# DC309A_CPLD.net
KiCad netlist of a schematic drawn in Altium Designer
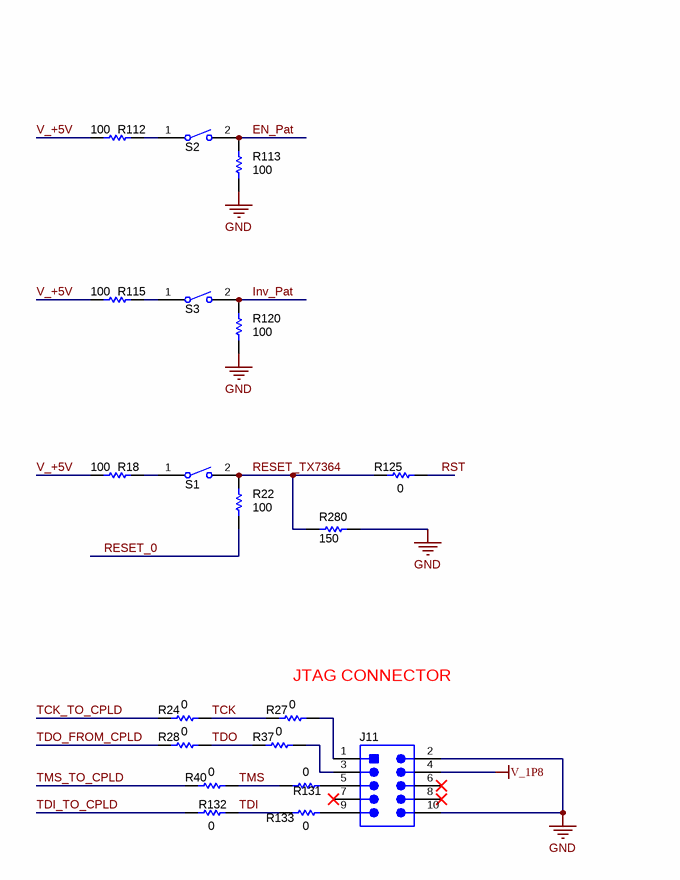
[diagram p0: DC309A_CPLD.SchDoc, top left]
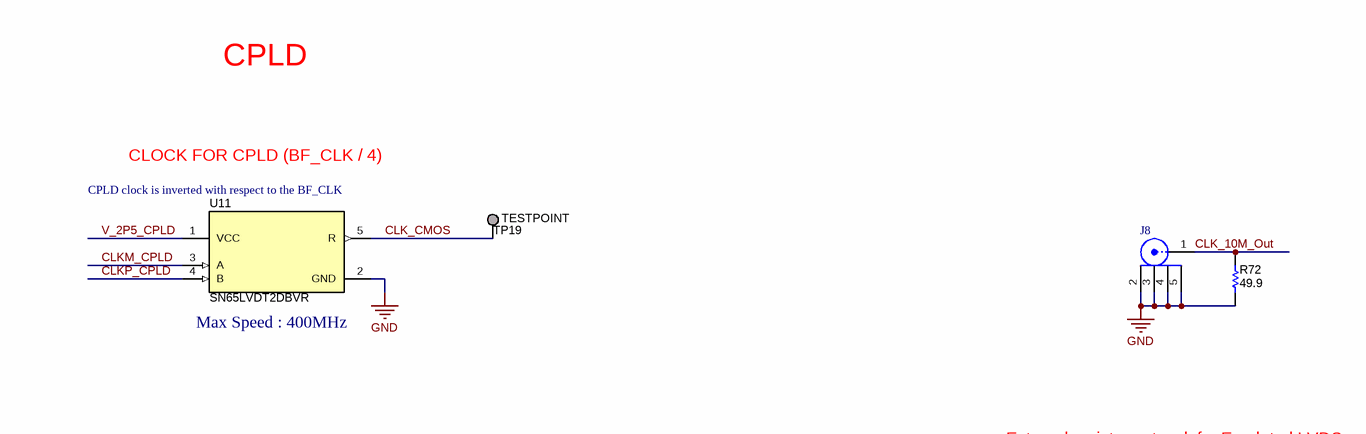
[diagram p1: DC309A_CPLD.SchDoc, top right]
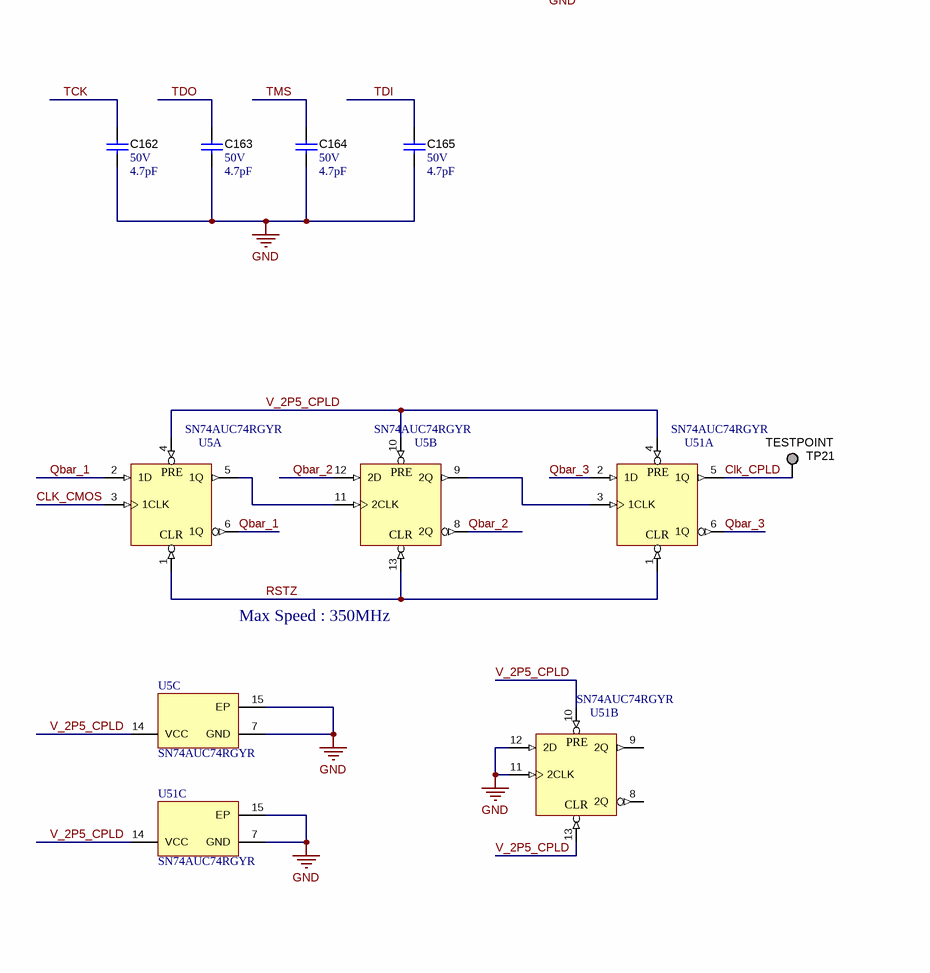
[diagram p2: DC309A_CPLD.SchDoc, bottom left]
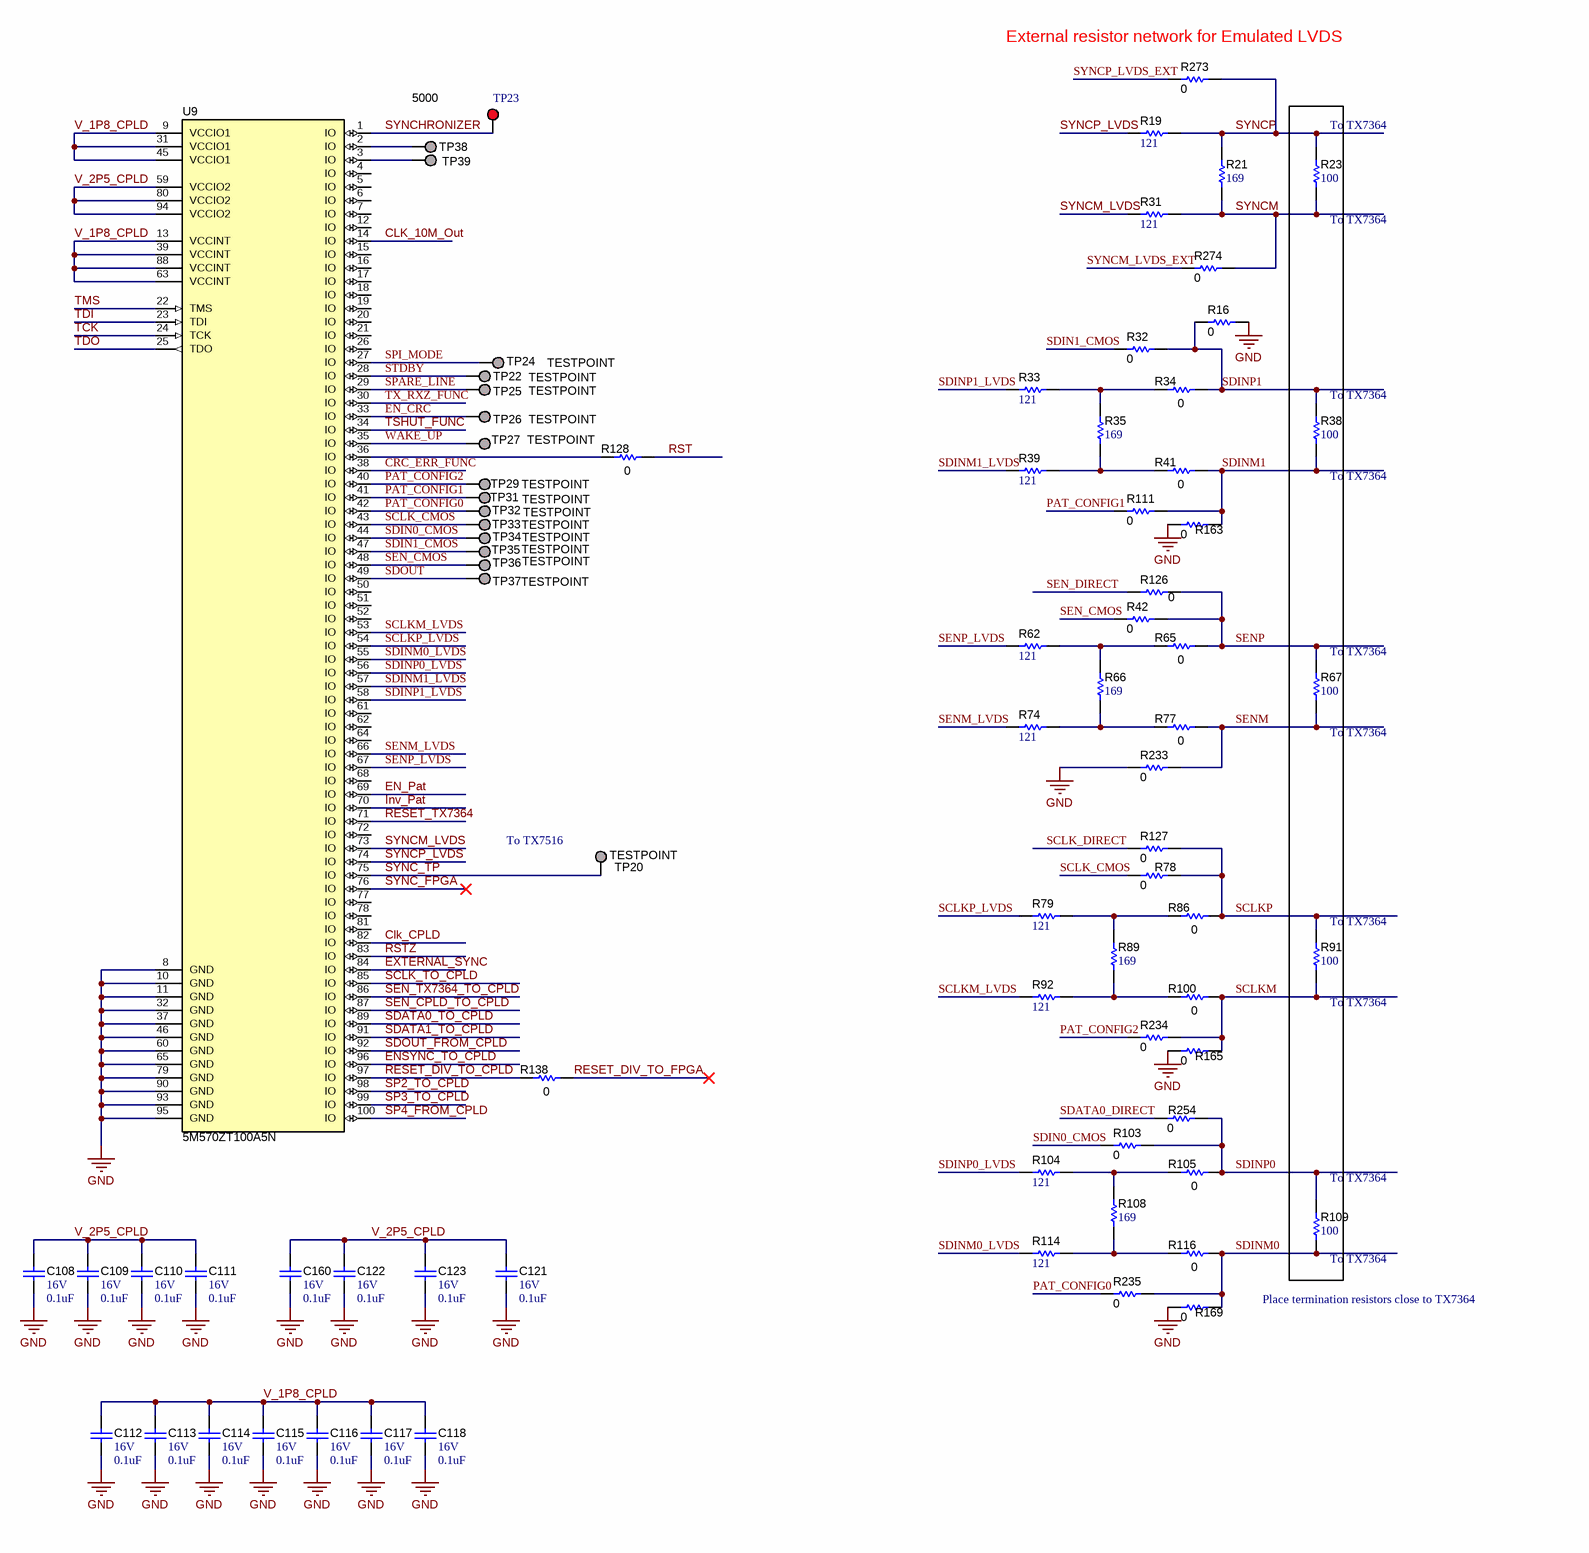
[diagram p3: DC309A_CPLD.SchDoc, bottom right]

(export (version "E")
  (design (tool "Eeschema 10.0.6"))
  (components
    (comp (ref "C108")
      (value "0402YC104KAT2A")
      (footprint "0402")
      (description "CAP, CERM, 0.1 uF, 16 V, +/- 10%, X7R, 0402")
      (fields
        (field (name "MANUFACTURER") "AVX")
        (field (name "VDC_V") "16V")
        (field (name "VALUEDISPLAYED") "0.1uF")
        (field (name "PUBLISHER") "Texas Instruments")
      )
      (libsource (lib "Altium Vault - TI") (part "Capacitor"))
    )
    (comp (ref "C109")
      (value "0402YC104KAT2A")
      (footprint "0402")
      (description "CAP, CERM, 0.1 uF, 16 V, +/- 10%, X7R, 0402")
      (fields
        (field (name "MANUFACTURER") "AVX")
        (field (name "VDC_V") "16V")
        (field (name "VALUEDISPLAYED") "0.1uF")
        (field (name "PUBLISHER") "Texas Instruments")
      )
      (libsource (lib "Altium Vault - TI") (part "Capacitor"))
    )
    (comp (ref "C110")
      (value "0402YC104KAT2A")
      (footprint "0402")
      (description "CAP, CERM, 0.1 uF, 16 V, +/- 10%, X7R, 0402")
      (fields
        (field (name "MANUFACTURER") "AVX")
        (field (name "VDC_V") "16V")
        (field (name "VALUEDISPLAYED") "0.1uF")
        (field (name "PUBLISHER") "Texas Instruments")
      )
      (libsource (lib "Altium Vault - TI") (part "Capacitor"))
    )
    (comp (ref "C111")
      (value "0402YC104KAT2A")
      (footprint "0402")
      (description "CAP, CERM, 0.1 uF, 16 V, +/- 10%, X7R, 0402")
      (fields
        (field (name "MANUFACTURER") "AVX")
        (field (name "VDC_V") "16V")
        (field (name "VALUEDISPLAYED") "0.1uF")
        (field (name "PUBLISHER") "Texas Instruments")
      )
      (libsource (lib "Altium Vault - TI") (part "Capacitor"))
    )
    (comp (ref "C112")
      (value "0402YC104KAT2A")
      (footprint "0402")
      (description "CAP, CERM, 0.1 uF, 16 V, +/- 10%, X7R, 0402")
      (fields
        (field (name "MANUFACTURER") "AVX")
        (field (name "VDC_V") "16V")
        (field (name "VALUEDISPLAYED") "0.1uF")
        (field (name "PUBLISHER") "Texas Instruments")
      )
      (libsource (lib "Altium Vault - TI") (part "Capacitor"))
    )
    (comp (ref "C113")
      (value "0402YC104KAT2A")
      (footprint "0402")
      (description "CAP, CERM, 0.1 uF, 16 V, +/- 10%, X7R, 0402")
      (fields
        (field (name "MANUFACTURER") "AVX")
        (field (name "VDC_V") "16V")
        (field (name "VALUEDISPLAYED") "0.1uF")
        (field (name "PUBLISHER") "Texas Instruments")
      )
      (libsource (lib "Altium Vault - TI") (part "Capacitor"))
    )
    (comp (ref "C114")
      (value "0402YC104KAT2A")
      (footprint "0402")
      (description "CAP, CERM, 0.1 uF, 16 V, +/- 10%, X7R, 0402")
      (fields
        (field (name "MANUFACTURER") "AVX")
        (field (name "VDC_V") "16V")
        (field (name "VALUEDISPLAYED") "0.1uF")
        (field (name "PUBLISHER") "Texas Instruments")
      )
      (libsource (lib "Altium Vault - TI") (part "Capacitor"))
    )
    (comp (ref "C115")
      (value "0402YC104KAT2A")
      (footprint "0402")
      (description "CAP, CERM, 0.1 uF, 16 V, +/- 10%, X7R, 0402")
      (fields
        (field (name "MANUFACTURER") "AVX")
        (field (name "VDC_V") "16V")
        (field (name "VALUEDISPLAYED") "0.1uF")
        (field (name "PUBLISHER") "Texas Instruments")
      )
      (libsource (lib "Altium Vault - TI") (part "Capacitor"))
    )
    (comp (ref "C116")
      (value "0402YC104KAT2A")
      (footprint "0402")
      (description "CAP, CERM, 0.1 uF, 16 V, +/- 10%, X7R, 0402")
      (fields
        (field (name "MANUFACTURER") "AVX")
        (field (name "VDC_V") "16V")
        (field (name "VALUEDISPLAYED") "0.1uF")
        (field (name "PUBLISHER") "Texas Instruments")
      )
      (libsource (lib "Altium Vault - TI") (part "Capacitor"))
    )
    (comp (ref "C117")
      (value "0402YC104KAT2A")
      (footprint "0402")
      (description "CAP, CERM, 0.1 uF, 16 V, +/- 10%, X7R, 0402")
      (fields
        (field (name "MANUFACTURER") "AVX")
        (field (name "VDC_V") "16V")
        (field (name "VALUEDISPLAYED") "0.1uF")
        (field (name "PUBLISHER") "Texas Instruments")
      )
      (libsource (lib "Altium Vault - TI") (part "Capacitor"))
    )
    (comp (ref "C118")
      (value "0402YC104KAT2A")
      (footprint "0402")
      (description "CAP, CERM, 0.1 uF, 16 V, +/- 10%, X7R, 0402")
      (fields
        (field (name "MANUFACTURER") "AVX")
        (field (name "VDC_V") "16V")
        (field (name "VALUEDISPLAYED") "0.1uF")
        (field (name "PUBLISHER") "Texas Instruments")
      )
      (libsource (lib "Altium Vault - TI") (part "Capacitor"))
    )
    (comp (ref "C121")
      (value "0402YC104KAT2A")
      (footprint "0402")
      (description "CAP, CERM, 0.1 uF, 16 V, +/- 10%, X7R, 0402")
      (fields
        (field (name "MANUFACTURER") "AVX")
        (field (name "VDC_V") "16V")
        (field (name "VALUEDISPLAYED") "0.1uF")
        (field (name "PUBLISHER") "Texas Instruments")
      )
      (libsource (lib "Altium Vault - TI") (part "Capacitor"))
    )
    (comp (ref "C122")
      (value "0402YC104KAT2A")
      (footprint "0402")
      (description "CAP, CERM, 0.1 uF, 16 V, +/- 10%, X7R, 0402")
      (fields
        (field (name "MANUFACTURER") "AVX")
        (field (name "VDC_V") "16V")
        (field (name "VALUEDISPLAYED") "0.1uF")
        (field (name "PUBLISHER") "Texas Instruments")
      )
      (libsource (lib "Altium Vault - TI") (part "Capacitor"))
    )
    (comp (ref "C123")
      (value "0402YC104KAT2A")
      (footprint "0402")
      (description "CAP, CERM, 0.1 uF, 16 V, +/- 10%, X7R, 0402")
      (fields
        (field (name "MANUFACTURER") "AVX")
        (field (name "VDC_V") "16V")
        (field (name "VALUEDISPLAYED") "0.1uF")
        (field (name "PUBLISHER") "Texas Instruments")
      )
      (libsource (lib "Altium Vault - TI") (part "Capacitor"))
    )
    (comp (ref "C160")
      (value "0402YC104KAT2A")
      (footprint "0402")
      (description "CAP, CERM, 0.1 uF, 16 V, +/- 10%, X7R, 0402")
      (fields
        (field (name "MANUFACTURER") "AVX")
        (field (name "VDC_V") "16V")
        (field (name "VALUEDISPLAYED") "0.1uF")
        (field (name "PUBLISHER") "Texas Instruments")
      )
      (libsource (lib "Altium Vault - TI") (part "Capacitor"))
    )
    (comp (ref "C162")
      (value "06035A4R7CAT2A")
      (footprint "0603")
      (description "CAP, CERM, 4.7 pF, 50 V, +/- 5%, C0G/NP0, 0603")
      (fields
        (field (name "MANUFACTURER") "AVX")
        (field (name "VDC_V") "50V")
        (field (name "VALUEDISPLAYED") "4.7pF")
        (field (name "PUBLISHER") "Texas Instruments")
      )
      (libsource (lib "Altium Vault - TI") (part "Capacitor"))
    )
    (comp (ref "C163")
      (value "06035A4R7CAT2A")
      (footprint "0603")
      (description "CAP, CERM, 4.7 pF, 50 V, +/- 5%, C0G/NP0, 0603")
      (fields
        (field (name "MANUFACTURER") "AVX")
        (field (name "VDC_V") "50V")
        (field (name "VALUEDISPLAYED") "4.7pF")
        (field (name "PUBLISHER") "Texas Instruments")
      )
      (libsource (lib "Altium Vault - TI") (part "Capacitor"))
    )
    (comp (ref "C164")
      (value "06035A4R7CAT2A")
      (footprint "0603")
      (description "CAP, CERM, 4.7 pF, 50 V, +/- 5%, C0G/NP0, 0603")
      (fields
        (field (name "MANUFACTURER") "AVX")
        (field (name "VDC_V") "50V")
        (field (name "VALUEDISPLAYED") "4.7pF")
        (field (name "PUBLISHER") "Texas Instruments")
      )
      (libsource (lib "Altium Vault - TI") (part "Capacitor"))
    )
    (comp (ref "C165")
      (value "06035A4R7CAT2A")
      (footprint "0603")
      (description "CAP, CERM, 4.7 pF, 50 V, +/- 5%, C0G/NP0, 0603")
      (fields
        (field (name "MANUFACTURER") "AVX")
        (field (name "VDC_V") "50V")
        (field (name "VALUEDISPLAYED") "4.7pF")
        (field (name "PUBLISHER") "Texas Instruments")
      )
      (libsource (lib "Altium Vault - TI") (part "Capacitor"))
    )
    (comp (ref "J8")
      (value "901-144-8RFX")
      (footprint "AMPHENOL_901-144-8RFX")
      (description "SMA Straight Jack, Gold, 50 Ohm, TH")
      (fields (field (name "MANUFACTURER") "Amphenol RF") (field (name "PUBLISHER") "Texas Instruments"))
      (libsource (lib "Altium Vault - TI") (part "SMA_Contact1_GND2345"))
    )
    (comp (ref "J11")
      (value "TSW-105-07-F-D")
      (footprint "Samtec_TSW-105-07-x-D")
      (description "Header, 2.54mm, 5x2, Gold, Black, TH")
      (fields (field (name "MANUFACTURER") "Samtec"))
      (libsource (lib "Altium Vault - TI") (part "Header_5x2"))
    )
    (comp (ref "R16")
      (value "0")
      (footprint "0402")
      (description "RES, 0, 5%, 0.1 W, AEC-Q200 Grade 0, 0402")
      (fields (field (name "PARTNUMBER") "ERJ-2GE0R00X") (field (name "MANUFACTURER") "Panasonic"))
      (libsource (lib "Altium Vault - TI") (part "CMP-0026992-3"))
    )
    (comp (ref "R18")
      (value "Resistor")
      (footprint "0402")
      (description "RES, 100, 5%, 0.063 W, AEC-Q200 Grade 0, 0402")
      (fields
        (field (name "PARTNUMBER") "CRCW0402100RJNED")
        (field (name "MANUFACTURER") "Vishay-Dale")
        (field (name "RES_OHM") "100")
      )
      (libsource (lib "Altium Vault - TI") (part "CMP-0026824-3"))
    )
    (comp (ref "R19")
      (value "CRCW0402121RFKED")
      (footprint "0402")
      (description "RES, 121, 1%, 0.063 W, AEC-Q200 Grade 0, 0402")
      (fields (field (name "MANUFACTURER") "Vishay-Dale") (field (name "VALUEDISPLAYED") "121"))
      (libsource (lib "Altium Vault - TI") (part "Resistor"))
    )
    (comp (ref "R21")
      (value "CRCW0402169RFKED")
      (footprint "0402")
      (description "RES, 169, 1%, 0.063 W, AEC-Q200 Grade 0, 0402")
      (fields (field (name "MANUFACTURER") "Vishay-Dale") (field (name "VALUEDISPLAYED") "169"))
      (libsource (lib "Altium Vault - TI") (part "Resistor"))
    )
    (comp (ref "R22")
      (value "Resistor")
      (footprint "0402")
      (description "RES, 100, 5%, 0.063 W, AEC-Q200 Grade 0, 0402")
      (fields
        (field (name "PARTNUMBER") "CRCW0402100RJNED")
        (field (name "MANUFACTURER") "Vishay-Dale")
        (field (name "RES_OHM") "100")
      )
      (libsource (lib "Altium Vault - TI") (part "CMP-0026824-3"))
    )
    (comp (ref "R23")
      (value "CRCW0402100RFKED")
      (footprint "0402")
      (description "RES, 100, 1%, 0.063 W, AEC-Q200 Grade 0, 0402")
      (fields (field (name "MANUFACTURER") "Vishay-Dale") (field (name "VALUEDISPLAYED") "100"))
      (libsource (lib "Altium Vault - TI") (part "Resistor"))
    )
    (comp (ref "R24")
      (value "0")
      (footprint "0402")
      (description "RES, 0, 5%, 0.1 W, AEC-Q200 Grade 0, 0402")
      (fields (field (name "PARTNUMBER") "ERJ-2GE0R00X") (field (name "MANUFACTURER") "Panasonic"))
      (libsource (lib "Altium Vault - TI") (part "CMP-0026992-3"))
    )
    (comp (ref "R27")
      (value "0")
      (footprint "0402")
      (description "RES, 0, 5%, 0.1 W, AEC-Q200 Grade 0, 0402")
      (fields (field (name "PARTNUMBER") "ERJ-2GE0R00X") (field (name "MANUFACTURER") "Panasonic"))
      (libsource (lib "Altium Vault - TI") (part "CMP-0026992-3"))
    )
    (comp (ref "R28")
      (value "0")
      (footprint "0402")
      (description "RES, 0, 5%, 0.1 W, AEC-Q200 Grade 0, 0402")
      (fields (field (name "PARTNUMBER") "ERJ-2GE0R00X") (field (name "MANUFACTURER") "Panasonic"))
      (libsource (lib "Altium Vault - TI") (part "CMP-0026992-3"))
    )
    (comp (ref "R31")
      (value "CRCW0402121RFKED")
      (footprint "0402")
      (description "RES, 121, 1%, 0.063 W, AEC-Q200 Grade 0, 0402")
      (fields (field (name "MANUFACTURER") "Vishay-Dale") (field (name "VALUEDISPLAYED") "121"))
      (libsource (lib "Altium Vault - TI") (part "Resistor"))
    )
    (comp (ref "R32")
      (value "0")
      (footprint "0402")
      (description "RES, 0, 5%, 0.1 W, AEC-Q200 Grade 0, 0402")
      (fields (field (name "PARTNUMBER") "ERJ-2GE0R00X") (field (name "MANUFACTURER") "Panasonic"))
      (libsource (lib "Altium Vault - TI") (part "CMP-0026992-3"))
    )
    (comp (ref "R33")
      (value "CRCW0402121RFKED")
      (footprint "0402")
      (description "RES, 121, 1%, 0.063 W, AEC-Q200 Grade 0, 0402")
      (fields (field (name "MANUFACTURER") "Vishay-Dale") (field (name "VALUEDISPLAYED") "121"))
      (libsource (lib "Altium Vault - TI") (part "Resistor"))
    )
    (comp (ref "R34")
      (value "0")
      (footprint "0402")
      (description "RES, 0, 5%, 0.1 W, AEC-Q200 Grade 0, 0402")
      (fields (field (name "PARTNUMBER") "ERJ-2GE0R00X") (field (name "MANUFACTURER") "Panasonic"))
      (libsource (lib "Altium Vault - TI") (part "CMP-0026992-3"))
    )
    (comp (ref "R35")
      (value "CRCW0402169RFKED")
      (footprint "0402")
      (description "RES, 169, 1%, 0.063 W, AEC-Q200 Grade 0, 0402")
      (fields (field (name "MANUFACTURER") "Vishay-Dale") (field (name "VALUEDISPLAYED") "169"))
      (libsource (lib "Altium Vault - TI") (part "Resistor"))
    )
    (comp (ref "R37")
      (value "0")
      (footprint "0402")
      (description "RES, 0, 5%, 0.1 W, AEC-Q200 Grade 0, 0402")
      (fields (field (name "PARTNUMBER") "ERJ-2GE0R00X") (field (name "MANUFACTURER") "Panasonic"))
      (libsource (lib "Altium Vault - TI") (part "CMP-0026992-3"))
    )
    (comp (ref "R38")
      (value "CRCW0402100RFKED")
      (footprint "0402")
      (description "RES, 100, 1%, 0.063 W, AEC-Q200 Grade 0, 0402")
      (fields (field (name "MANUFACTURER") "Vishay-Dale") (field (name "VALUEDISPLAYED") "100"))
      (libsource (lib "Altium Vault - TI") (part "Resistor"))
    )
    (comp (ref "R39")
      (value "CRCW0402121RFKED")
      (footprint "0402")
      (description "RES, 121, 1%, 0.063 W, AEC-Q200 Grade 0, 0402")
      (fields (field (name "MANUFACTURER") "Vishay-Dale") (field (name "VALUEDISPLAYED") "121"))
      (libsource (lib "Altium Vault - TI") (part "Resistor"))
    )
    (comp (ref "R40")
      (value "0")
      (footprint "0402")
      (description "RES, 0, 5%, 0.1 W, AEC-Q200 Grade 0, 0402")
      (fields (field (name "PARTNUMBER") "ERJ-2GE0R00X") (field (name "MANUFACTURER") "Panasonic"))
      (libsource (lib "Altium Vault - TI") (part "CMP-0026992-3"))
    )
    (comp (ref "R41")
      (value "0")
      (footprint "0402")
      (description "RES, 0, 5%, 0.1 W, AEC-Q200 Grade 0, 0402")
      (fields (field (name "PARTNUMBER") "ERJ-2GE0R00X") (field (name "MANUFACTURER") "Panasonic"))
      (libsource (lib "Altium Vault - TI") (part "CMP-0026992-3"))
    )
    (comp (ref "R42")
      (value "0")
      (footprint "0402")
      (description "RES, 0, 5%, 0.1 W, AEC-Q200 Grade 0, 0402")
      (fields (field (name "PARTNUMBER") "ERJ-2GE0R00X") (field (name "MANUFACTURER") "Panasonic"))
      (libsource (lib "Altium Vault - TI") (part "CMP-0026992-3"))
    )
    (comp (ref "R62")
      (value "CRCW0402121RFKED")
      (footprint "0402")
      (description "RES, 121, 1%, 0.063 W, AEC-Q200 Grade 0, 0402")
      (fields (field (name "MANUFACTURER") "Vishay-Dale") (field (name "VALUEDISPLAYED") "121"))
      (libsource (lib "Altium Vault - TI") (part "Resistor"))
    )
    (comp (ref "R65")
      (value "0")
      (footprint "0402")
      (description "RES, 0, 5%, 0.1 W, AEC-Q200 Grade 0, 0402")
      (fields (field (name "PARTNUMBER") "ERJ-2GE0R00X") (field (name "MANUFACTURER") "Panasonic"))
      (libsource (lib "Altium Vault - TI") (part "CMP-0026992-3"))
    )
    (comp (ref "R66")
      (value "CRCW0402169RFKED")
      (footprint "0402")
      (description "RES, 169, 1%, 0.063 W, AEC-Q200 Grade 0, 0402")
      (fields (field (name "MANUFACTURER") "Vishay-Dale") (field (name "VALUEDISPLAYED") "169"))
      (libsource (lib "Altium Vault - TI") (part "Resistor"))
    )
    (comp (ref "R67")
      (value "CRCW0402100RFKED")
      (footprint "0402")
      (description "RES, 100, 1%, 0.063 W, AEC-Q200 Grade 0, 0402")
      (fields (field (name "MANUFACTURER") "Vishay-Dale") (field (name "VALUEDISPLAYED") "100"))
      (libsource (lib "Altium Vault - TI") (part "Resistor"))
    )
    (comp (ref "R72")
      (value "TNPW060349R9BEEA")
      (footprint "TNPW0603")
      (description "RES, 49.9, 0.1%, 0.1 W, AEC-Q200 Grade 1, 0603")
      (fields
        (field (name "MANUFACTURER") "Vishay-Dale")
        (field (name "VALUEDISPLAYED") "49.9")
        (field (name "PUBLISHER") "Texas Instruments")
      )
      (libsource (lib "Altium Vault - TI") (part "Resistor"))
    )
    (comp (ref "R74")
      (value "CRCW0402121RFKED")
      (footprint "0402")
      (description "RES, 121, 1%, 0.063 W, AEC-Q200 Grade 0, 0402")
      (fields (field (name "MANUFACTURER") "Vishay-Dale") (field (name "VALUEDISPLAYED") "121"))
      (libsource (lib "Altium Vault - TI") (part "Resistor"))
    )
    (comp (ref "R77")
      (value "0")
      (footprint "0402")
      (description "RES, 0, 5%, 0.1 W, AEC-Q200 Grade 0, 0402")
      (fields (field (name "PARTNUMBER") "ERJ-2GE0R00X") (field (name "MANUFACTURER") "Panasonic"))
      (libsource (lib "Altium Vault - TI") (part "CMP-0026992-3"))
    )
    (comp (ref "R78")
      (value "0")
      (footprint "0402")
      (description "RES, 0, 5%, 0.1 W, AEC-Q200 Grade 0, 0402")
      (fields (field (name "PARTNUMBER") "ERJ-2GE0R00X") (field (name "MANUFACTURER") "Panasonic"))
      (libsource (lib "Altium Vault - TI") (part "CMP-0026992-3"))
    )
    (comp (ref "R79")
      (value "CRCW0402121RFKED")
      (footprint "0402")
      (description "RES, 121, 1%, 0.063 W, AEC-Q200 Grade 0, 0402")
      (fields (field (name "MANUFACTURER") "Vishay-Dale") (field (name "VALUEDISPLAYED") "121"))
      (libsource (lib "Altium Vault - TI") (part "Resistor"))
    )
    (comp (ref "R86")
      (value "0")
      (footprint "0402")
      (description "RES, 0, 5%, 0.1 W, AEC-Q200 Grade 0, 0402")
      (fields (field (name "PARTNUMBER") "ERJ-2GE0R00X") (field (name "MANUFACTURER") "Panasonic"))
      (libsource (lib "Altium Vault - TI") (part "CMP-0026992-3"))
    )
    (comp (ref "R89")
      (value "CRCW0402169RFKED")
      (footprint "0402")
      (description "RES, 169, 1%, 0.063 W, AEC-Q200 Grade 0, 0402")
      (fields (field (name "MANUFACTURER") "Vishay-Dale") (field (name "VALUEDISPLAYED") "169"))
      (libsource (lib "Altium Vault - TI") (part "Resistor"))
    )
    (comp (ref "R91")
      (value "CRCW0402100RFKED")
      (footprint "0402")
      (description "RES, 100, 1%, 0.063 W, AEC-Q200 Grade 0, 0402")
      (fields (field (name "MANUFACTURER") "Vishay-Dale") (field (name "VALUEDISPLAYED") "100"))
      (libsource (lib "Altium Vault - TI") (part "Resistor"))
    )
    (comp (ref "R92")
      (value "CRCW0402121RFKED")
      (footprint "0402")
      (description "RES, 121, 1%, 0.063 W, AEC-Q200 Grade 0, 0402")
      (fields (field (name "MANUFACTURER") "Vishay-Dale") (field (name "VALUEDISPLAYED") "121"))
      (libsource (lib "Altium Vault - TI") (part "Resistor"))
    )
    (comp (ref "R100")
      (value "0")
      (footprint "0402")
      (description "RES, 0, 5%, 0.1 W, AEC-Q200 Grade 0, 0402")
      (fields (field (name "PARTNUMBER") "ERJ-2GE0R00X") (field (name "MANUFACTURER") "Panasonic"))
      (libsource (lib "Altium Vault - TI") (part "CMP-0026992-3"))
    )
    (comp (ref "R103")
      (value "0")
      (footprint "0402")
      (description "RES, 0, 5%, 0.1 W, AEC-Q200 Grade 0, 0402")
      (fields (field (name "PARTNUMBER") "ERJ-2GE0R00X") (field (name "MANUFACTURER") "Panasonic"))
      (libsource (lib "Altium Vault - TI") (part "CMP-0026992-3"))
    )
    (comp (ref "R104")
      (value "CRCW0402121RFKED")
      (footprint "0402")
      (description "RES, 121, 1%, 0.063 W, AEC-Q200 Grade 0, 0402")
      (fields (field (name "MANUFACTURER") "Vishay-Dale") (field (name "VALUEDISPLAYED") "121"))
      (libsource (lib "Altium Vault - TI") (part "Resistor"))
    )
    (comp (ref "R105")
      (value "0")
      (footprint "0402")
      (description "RES, 0, 5%, 0.1 W, AEC-Q200 Grade 0, 0402")
      (fields (field (name "PARTNUMBER") "ERJ-2GE0R00X") (field (name "MANUFACTURER") "Panasonic"))
      (libsource (lib "Altium Vault - TI") (part "CMP-0026992-3"))
    )
    (comp (ref "R108")
      (value "CRCW0402169RFKED")
      (footprint "0402")
      (description "RES, 169, 1%, 0.063 W, AEC-Q200 Grade 0, 0402")
      (fields (field (name "MANUFACTURER") "Vishay-Dale") (field (name "VALUEDISPLAYED") "169"))
      (libsource (lib "Altium Vault - TI") (part "Resistor"))
    )
    (comp (ref "R109")
      (value "CRCW0402100RFKED")
      (footprint "0402")
      (description "RES, 100, 1%, 0.063 W, AEC-Q200 Grade 0, 0402")
      (fields (field (name "MANUFACTURER") "Vishay-Dale") (field (name "VALUEDISPLAYED") "100"))
      (libsource (lib "Altium Vault - TI") (part "Resistor"))
    )
    (comp (ref "R111")
      (value "0")
      (footprint "0402")
      (description "RES, 0, 5%, 0.1 W, AEC-Q200 Grade 0, 0402")
      (fields (field (name "PARTNUMBER") "ERJ-2GE0R00X") (field (name "MANUFACTURER") "Panasonic"))
      (libsource (lib "Altium Vault - TI") (part "CMP-0026992-3"))
    )
    (comp (ref "R112")
      (value "Resistor")
      (footprint "0402")
      (description "RES, 100, 5%, 0.063 W, AEC-Q200 Grade 0, 0402")
      (fields
        (field (name "PARTNUMBER") "CRCW0402100RJNED")
        (field (name "MANUFACTURER") "Vishay-Dale")
        (field (name "RES_OHM") "100")
      )
      (libsource (lib "Altium Vault - TI") (part "CMP-0026824-3"))
    )
    (comp (ref "R113")
      (value "Resistor")
      (footprint "0402")
      (description "RES, 100, 5%, 0.063 W, AEC-Q200 Grade 0, 0402")
      (fields
        (field (name "PARTNUMBER") "CRCW0402100RJNED")
        (field (name "MANUFACTURER") "Vishay-Dale")
        (field (name "RES_OHM") "100")
      )
      (libsource (lib "Altium Vault - TI") (part "CMP-0026824-3"))
    )
    (comp (ref "R114")
      (value "CRCW0402121RFKED")
      (footprint "0402")
      (description "RES, 121, 1%, 0.063 W, AEC-Q200 Grade 0, 0402")
      (fields (field (name "MANUFACTURER") "Vishay-Dale") (field (name "VALUEDISPLAYED") "121"))
      (libsource (lib "Altium Vault - TI") (part "Resistor"))
    )
    (comp (ref "R115")
      (value "Resistor")
      (footprint "0402")
      (description "RES, 100, 5%, 0.063 W, AEC-Q200 Grade 0, 0402")
      (fields
        (field (name "PARTNUMBER") "CRCW0402100RJNED")
        (field (name "MANUFACTURER") "Vishay-Dale")
        (field (name "RES_OHM") "100")
      )
      (libsource (lib "Altium Vault - TI") (part "CMP-0026824-3"))
    )
    (comp (ref "R116")
      (value "0")
      (footprint "0402")
      (description "RES, 0, 5%, 0.1 W, AEC-Q200 Grade 0, 0402")
      (fields (field (name "PARTNUMBER") "ERJ-2GE0R00X") (field (name "MANUFACTURER") "Panasonic"))
      (libsource (lib "Altium Vault - TI") (part "CMP-0026992-3"))
    )
    (comp (ref "R120")
      (value "Resistor")
      (footprint "0402")
      (description "RES, 100, 5%, 0.063 W, AEC-Q200 Grade 0, 0402")
      (fields
        (field (name "PARTNUMBER") "CRCW0402100RJNED")
        (field (name "MANUFACTURER") "Vishay-Dale")
        (field (name "RES_OHM") "100")
      )
      (libsource (lib "Altium Vault - TI") (part "CMP-0026824-3"))
    )
    (comp (ref "R125")
      (value "0")
      (footprint "0402")
      (description "RES, 0, 5%, 0.1 W, AEC-Q200 Grade 0, 0402")
      (fields (field (name "PARTNUMBER") "ERJ-2GE0R00X") (field (name "MANUFACTURER") "Panasonic"))
      (libsource (lib "Altium Vault - TI") (part "CMP-0026992-3"))
    )
    (comp (ref "R126")
      (value "0")
      (footprint "0402")
      (description "RES, 0, 5%, 0.1 W, AEC-Q200 Grade 0, 0402")
      (fields (field (name "PARTNUMBER") "ERJ-2GE0R00X") (field (name "MANUFACTURER") "Panasonic"))
      (libsource (lib "Altium Vault - TI") (part "CMP-0026992-3"))
    )
    (comp (ref "R127")
      (value "0")
      (footprint "0402")
      (description "RES, 0, 5%, 0.1 W, AEC-Q200 Grade 0, 0402")
      (fields (field (name "PARTNUMBER") "ERJ-2GE0R00X") (field (name "MANUFACTURER") "Panasonic"))
      (libsource (lib "Altium Vault - TI") (part "CMP-0026992-3"))
    )
    (comp (ref "R128")
      (value "0")
      (footprint "0402")
      (description "RES, 0, 5%, 0.1 W, AEC-Q200 Grade 0, 0402")
      (fields (field (name "PARTNUMBER") "ERJ-2GE0R00X") (field (name "MANUFACTURER") "Panasonic"))
      (libsource (lib "Altium Vault - TI") (part "CMP-0026992-3"))
    )
    (comp (ref "R131")
      (value "0")
      (footprint "0402")
      (description "RES, 0, 5%, 0.1 W, AEC-Q200 Grade 0, 0402")
      (fields (field (name "PARTNUMBER") "ERJ-2GE0R00X") (field (name "MANUFACTURER") "Panasonic"))
      (libsource (lib "Altium Vault - TI") (part "CMP-0026992-3"))
    )
    (comp (ref "R132")
      (value "0")
      (footprint "0402")
      (description "RES, 0, 5%, 0.1 W, AEC-Q200 Grade 0, 0402")
      (fields (field (name "PARTNUMBER") "ERJ-2GE0R00X") (field (name "MANUFACTURER") "Panasonic"))
      (libsource (lib "Altium Vault - TI") (part "CMP-0026992-3"))
    )
    (comp (ref "R133")
      (value "0")
      (footprint "0402")
      (description "RES, 0, 5%, 0.1 W, AEC-Q200 Grade 0, 0402")
      (fields (field (name "PARTNUMBER") "ERJ-2GE0R00X") (field (name "MANUFACTURER") "Panasonic"))
      (libsource (lib "Altium Vault - TI") (part "CMP-0026992-3"))
    )
    (comp (ref "R138")
      (value "0")
      (footprint "0402")
      (description "RES, 0, 5%, 0.1 W, AEC-Q200 Grade 0, 0402")
      (fields (field (name "PARTNUMBER") "ERJ-2GE0R00X") (field (name "MANUFACTURER") "Panasonic"))
      (libsource (lib "Altium Vault - TI") (part "CMP-0026992-3"))
    )
    (comp (ref "R163")
      (value "0")
      (footprint "0402")
      (description "RES, 0, 5%, 0.1 W, AEC-Q200 Grade 0, 0402")
      (fields (field (name "PARTNUMBER") "ERJ-2GE0R00X") (field (name "MANUFACTURER") "Panasonic"))
      (libsource (lib "Altium Vault - TI") (part "CMP-0026992-3"))
    )
    (comp (ref "R165")
      (value "0")
      (footprint "0402")
      (description "RES, 0, 5%, 0.1 W, AEC-Q200 Grade 0, 0402")
      (fields (field (name "PARTNUMBER") "ERJ-2GE0R00X") (field (name "MANUFACTURER") "Panasonic"))
      (libsource (lib "Altium Vault - TI") (part "CMP-0026992-3"))
    )
    (comp (ref "R169")
      (value "0")
      (footprint "0402")
      (description "RES, 0, 5%, 0.1 W, AEC-Q200 Grade 0, 0402")
      (fields (field (name "PARTNUMBER") "ERJ-2GE0R00X") (field (name "MANUFACTURER") "Panasonic"))
      (libsource (lib "Altium Vault - TI") (part "CMP-0026992-3"))
    )
    (comp (ref "R233")
      (value "0")
      (footprint "0402")
      (description "RES, 0, 5%, 0.1 W, AEC-Q200 Grade 0, 0402")
      (fields (field (name "PARTNUMBER") "ERJ-2GE0R00X") (field (name "MANUFACTURER") "Panasonic"))
      (libsource (lib "Altium Vault - TI") (part "CMP-0026992-3"))
    )
    (comp (ref "R234")
      (value "0")
      (footprint "0402")
      (description "RES, 0, 5%, 0.1 W, AEC-Q200 Grade 0, 0402")
      (fields (field (name "PARTNUMBER") "ERJ-2GE0R00X") (field (name "MANUFACTURER") "Panasonic"))
      (libsource (lib "Altium Vault - TI") (part "CMP-0026992-3"))
    )
    (comp (ref "R235")
      (value "0")
      (footprint "0402")
      (description "RES, 0, 5%, 0.1 W, AEC-Q200 Grade 0, 0402")
      (fields (field (name "PARTNUMBER") "ERJ-2GE0R00X") (field (name "MANUFACTURER") "Panasonic"))
      (libsource (lib "Altium Vault - TI") (part "CMP-0026992-3"))
    )
    (comp (ref "R254")
      (value "0")
      (footprint "0402")
      (description "RES, 0, 5%, 0.1 W, AEC-Q200 Grade 0, 0402")
      (fields (field (name "PARTNUMBER") "ERJ-2GE0R00X") (field (name "MANUFACTURER") "Panasonic"))
      (libsource (lib "Altium Vault - TI") (part "CMP-0026992-3"))
    )
    (comp (ref "R273")
      (value "0")
      (footprint "0402")
      (description "RES, 0, 5%, 0.1 W, AEC-Q200 Grade 0, 0402")
      (fields (field (name "PARTNUMBER") "ERJ-2GE0R00X") (field (name "MANUFACTURER") "Panasonic"))
      (libsource (lib "Altium Vault - TI") (part "CMP-0026992-3"))
    )
    (comp (ref "R274")
      (value "0")
      (footprint "0402")
      (description "RES, 0, 5%, 0.1 W, AEC-Q200 Grade 0, 0402")
      (fields (field (name "PARTNUMBER") "ERJ-2GE0R00X") (field (name "MANUFACTURER") "Panasonic"))
      (libsource (lib "Altium Vault - TI") (part "CMP-0026992-3"))
    )
    (comp (ref "R280")
      (value "RT0603BRD07150RL")
      (footprint "0603")
      (description "RES, 150, 0.1%, 0.1 W, 0603")
      (fields
        (field (name "MANUFACTURER") "Yageo America")
        (field (name "VALUEDISPLAYED") "150")
        (field (name "PUBLISHER") "Texas Instruments")
      )
      (libsource (lib "Altium Vault - TI") (part "Resistor"))
    )
    (comp (ref "S1")
      (value "SW_SPST-single")
      (footprint "SW_EVQ5PN04K")
      (description "Switch, SPST-NO, Off-Mom, 0.05 A, 12 VDC, SMD")
      (fields
        (field (name "PARTNUMBER") "EVQ-5PN04K")
        (field (name "MANUFACTURER") "Panasonic")
        (field (name "PUBLISHER") "Texas Instruments")
      )
      (libsource (lib "Altium Vault - TI") (part "SW_SPST-single"))
    )
    (comp (ref "S2")
      (value "SW_SPST-single")
      (footprint "SW_EVQ5PN04K")
      (description "Switch, SPST-NO, Off-Mom, 0.05 A, 12 VDC, SMD")
      (fields
        (field (name "PARTNUMBER") "EVQ-5PN04K")
        (field (name "MANUFACTURER") "Panasonic")
        (field (name "PUBLISHER") "Texas Instruments")
      )
      (libsource (lib "Altium Vault - TI") (part "SW_SPST-single"))
    )
    (comp (ref "S3")
      (value "SW_SPST-single")
      (footprint "SW_EVQ5PN04K")
      (description "Switch, SPST-NO, Off-Mom, 0.05 A, 12 VDC, SMD")
      (fields
        (field (name "PARTNUMBER") "EVQ-5PN04K")
        (field (name "MANUFACTURER") "Panasonic")
        (field (name "PUBLISHER") "Texas Instruments")
      )
      (libsource (lib "Altium Vault - TI") (part "SW_SPST-single"))
    )
    (comp (ref "TP19")
      (value "TESTPOINT")
      (footprint "TP_50MIL-SMT")
      (description "TEST POINT.  No entry in BOM.")
      (libsource (lib "Altium Vault - TI") (part "TESTPOINT"))
    )
    (comp (ref "TP20")
      (value "TESTPOINT")
      (footprint "TP_50MIL-SMT")
      (description "TEST POINT.  No entry in BOM.")
      (libsource (lib "Altium Vault - TI") (part "TESTPOINT"))
    )
    (comp (ref "TP21")
      (value "TESTPOINT")
      (footprint "TP_50MIL-SMT")
      (description "TEST POINT.  No entry in BOM.")
      (libsource (lib "Altium Vault - TI") (part "TESTPOINT"))
    )
    (comp (ref "TP22")
      (value "TESTPOINT")
      (footprint "TP_50MIL-SMT")
      (description "TEST POINT.  No entry in BOM.")
      (libsource (lib "Altium Vault - TI") (part "TESTPOINT"))
    )
    (comp (ref "TP23")
      (value "5000")
      (footprint "Keystone5000")
      (description "Test Point, Miniature, Red, TH")
      (fields
        (field (name "MANUFACTURER") "Keystone Electronics")
        (field (name "PUBLISHER") "Texas Instruments")
      )
      (libsource (lib "Altium Vault - TI") (part "5000"))
    )
    (comp (ref "TP24")
      (value "TESTPOINT")
      (footprint "TP_50MIL-SMT")
      (description "TEST POINT.  No entry in BOM.")
      (libsource (lib "Altium Vault - TI") (part "TESTPOINT"))
    )
    (comp (ref "TP25")
      (value "TESTPOINT")
      (footprint "TP_50MIL-SMT")
      (description "TEST POINT.  No entry in BOM.")
      (libsource (lib "Altium Vault - TI") (part "TESTPOINT"))
    )
    (comp (ref "TP26")
      (value "TESTPOINT")
      (footprint "TP_50MIL-SMT")
      (description "TEST POINT.  No entry in BOM.")
      (libsource (lib "Altium Vault - TI") (part "TESTPOINT"))
    )
    (comp (ref "TP27")
      (value "TESTPOINT")
      (footprint "TP_50MIL-SMT")
      (description "TEST POINT.  No entry in BOM.")
      (libsource (lib "Altium Vault - TI") (part "TESTPOINT"))
    )
    (comp (ref "TP29")
      (value "TESTPOINT")
      (footprint "TP_50MIL-SMT")
      (description "TEST POINT.  No entry in BOM.")
      (libsource (lib "Altium Vault - TI") (part "TESTPOINT"))
    )
    (comp (ref "TP31")
      (value "TESTPOINT")
      (footprint "TP_50MIL-SMT")
      (description "TEST POINT.  No entry in BOM.")
      (libsource (lib "Altium Vault - TI") (part "TESTPOINT"))
    )
    (comp (ref "TP32")
      (value "TESTPOINT")
      (footprint "TP_50MIL-SMT")
      (description "TEST POINT.  No entry in BOM.")
      (libsource (lib "Altium Vault - TI") (part "TESTPOINT"))
    )
    (comp (ref "TP33")
      (value "TESTPOINT")
      (footprint "TP_50MIL-SMT")
      (description "TEST POINT.  No entry in BOM.")
      (libsource (lib "Altium Vault - TI") (part "TESTPOINT"))
    )
    (comp (ref "TP34")
      (value "TESTPOINT")
      (footprint "TP_50MIL-SMT")
      (description "TEST POINT.  No entry in BOM.")
      (libsource (lib "Altium Vault - TI") (part "TESTPOINT"))
    )
    (comp (ref "TP35")
      (value "TESTPOINT")
      (footprint "TP_50MIL-SMT")
      (description "TEST POINT.  No entry in BOM.")
      (libsource (lib "Altium Vault - TI") (part "TESTPOINT"))
    )
    (comp (ref "TP36")
      (value "TESTPOINT")
      (footprint "TP_50MIL-SMT")
      (description "TEST POINT.  No entry in BOM.")
      (libsource (lib "Altium Vault - TI") (part "TESTPOINT"))
    )
    (comp (ref "TP37")
      (value "TESTPOINT")
      (footprint "TP_50MIL-SMT")
      (description "TEST POINT.  No entry in BOM.")
      (libsource (lib "Altium Vault - TI") (part "TESTPOINT"))
    )
    (comp (ref "TP38")
      (value "TESTPOINT")
      (footprint "TP_50MIL-SMT")
      (description "TEST POINT.  No entry in BOM.")
      (libsource (lib "Altium Vault - TI") (part "TESTPOINT"))
    )
    (comp (ref "TP39")
      (value "TESTPOINT")
      (footprint "TP_50MIL-SMT")
      (description "TEST POINT.  No entry in BOM.")
      (libsource (lib "Altium Vault - TI") (part "TESTPOINT"))
    )
    (comp (ref "U5")
      (value "SN74AUC74RGYR")
      (footprint "RGY0014A")
      (description "Dual Positive-Edge-Triggered D-Type Flip-Flops with Clear and Preset, RGY0014A, LARGE T&R")
      (fields
        (field (name "MANUFACTURER") "Texas Instruments")
        (field (name "GENERIC PART NUMBER") "SN74AUC74")
        (field (name "PARTNUMBER") "SN74AUC74RGYR")
      )
      (libsource (lib "Altium Vault - TI") (part "TI-SN74XXXX74X-14"))
    )
    (comp (ref "U9")
      (value "5M570ZT100A5N")
      (footprint "TQFP100_14x14MM")
      (description "IC CPLD 440MC, TQFP-100")
      (fields (field (name "MANUFACTURER") "Altera"))
      (libsource (lib "Altium Vault - TI") (part "5M570ZT100A5N"))
    )
    (comp (ref "U11")
      (value "SN65LVDT2DBVR")
      (footprint "DBV0005A_N")
      (description "Single LVDS Receiver, DBV0005A (SOT-23-5)")
      (fields
        (field (name "ALTERNATE PARTNUMBER") "SN65LVDT2DBVT")
        (field (name "MANUFACTURER") "Texas Instruments")
        (field (name "PARTNUMBER") "SN65LVDT2DBVR")
        (field (name "PUBLISHER") "Texas Instruments")
      )
      (libsource (lib "Altium Vault - TI") (part "CMP-0065800-1"))
    )
    (comp (ref "U51")
      (value "SN74AUC74RGYR")
      (footprint "RGY0014A")
      (description "Dual Positive-Edge-Triggered D-Type Flip-Flops with Clear and Preset, RGY0014A, LARGE T&R")
      (fields
        (field (name "MANUFACTURER") "Texas Instruments")
        (field (name "GENERIC PART NUMBER") "SN74AUC74")
        (field (name "PARTNUMBER") "SN74AUC74RGYR")
      )
      (libsource (lib "Altium Vault - TI") (part "TI-SN74XXXX74X-14"))
    )
  )
  (nets
    (net (code "1") (name "/CLKM_CPLD") (class "Default")
      (node (ref "U11") (pin "3") (pinfunction "A_3") (pintype "input"))
    )
    (net (code "2") (name "/CLKP_CPLD") (class "Default")
      (node (ref "U11") (pin "4") (pinfunction "B_4") (pintype "input"))
    )
    (net (code "3") (name "/CLK_10M_Out") (class "Default")
      (node (ref "J8") (pin "1") (pinfunction "1_1") (pintype "passive"))
      (node (ref "R72") (pin "2") (pinfunction "2_2") (pintype "passive"))
      (node (ref "U9") (pin "14") (pinfunction "IO_14") (pintype "bidirectional"))
    )
    (net (code "4") (name "/CLK_CMOS") (class "Default")
      (node (ref "TP19") (pin "1") (pintype "passive"))
      (node (ref "U11") (pin "5") (pinfunction "R_5") (pintype "output"))
      (node (ref "U5") (pin "3") (pinfunction "1CLK_3") (pintype "input"))
    )
    (net (code "5") (name "/CRC_ERR_FUNC") (class "Default")
      (node (ref "U9") (pin "38") (pinfunction "IO_38") (pintype "bidirectional"))
    )
    (net (code "6") (name "/Clk_CPLD") (class "Default")
      (node (ref "TP21") (pin "1") (pintype "passive"))
      (node (ref "U51") (pin "5") (pinfunction "1Q_5") (pintype "output"))
      (node (ref "U9") (pin "82") (pinfunction "IO_82") (pintype "bidirectional"))
    )
    (net (code "7") (name "/ENSYNC_TO_CPLD") (class "Default")
      (node (ref "U9") (pin "96") (pinfunction "IO_96") (pintype "bidirectional"))
    )
    (net (code "8") (name "/EN_CRC") (class "Default")
      (node (ref "TP26") (pin "1") (pintype "passive"))
      (node (ref "U9") (pin "33") (pinfunction "IO_33") (pintype "bidirectional"))
    )
    (net (code "9") (name "/EN_Pat") (class "Default")
      (node (ref "R113") (pin "2") (pinfunction "2_2") (pintype "passive"))
      (node (ref "S2") (pin "2") (pinfunction "2_2") (pintype "passive"))
      (node (ref "U9") (pin "69") (pinfunction "IO_69") (pintype "bidirectional"))
    )
    (net (code "10") (name "/EXTERNAL_SYNC") (class "Default")
      (node (ref "U9") (pin "84") (pinfunction "IO_84") (pintype "bidirectional"))
    )
    (net (code "11") (name "/Inv_Pat") (class "Default")
      (node (ref "R120") (pin "2") (pinfunction "2_2") (pintype "passive"))
      (node (ref "S3") (pin "2") (pinfunction "2_2") (pintype "passive"))
      (node (ref "U9") (pin "70") (pinfunction "IO_70") (pintype "bidirectional"))
    )
    (net (code "12") (name "/PAT_CONFIG0") (class "Default")
      (node (ref "R235") (pin "2") (pinfunction "2_2") (pintype "passive"))
      (node (ref "TP32") (pin "1") (pintype "passive"))
      (node (ref "U9") (pin "42") (pinfunction "IO_42") (pintype "bidirectional"))
    )
    (net (code "13") (name "/PAT_CONFIG1") (class "Default")
      (node (ref "R111") (pin "2") (pinfunction "2_2") (pintype "passive"))
      (node (ref "TP31") (pin "1") (pintype "passive"))
      (node (ref "U9") (pin "41") (pinfunction "IO_41") (pintype "bidirectional"))
    )
    (net (code "14") (name "/PAT_CONFIG2") (class "Default")
      (node (ref "R234") (pin "2") (pinfunction "2_2") (pintype "passive"))
      (node (ref "TP29") (pin "1") (pintype "passive"))
      (node (ref "U9") (pin "40") (pinfunction "IO_40") (pintype "bidirectional"))
    )
    (net (code "15") (name "/Qbar_1") (class "Default")
      (node (ref "U5") (pin "2") (pinfunction "1D_2") (pintype "input"))
      (node (ref "U5") (pin "6") (pinfunction "1Q_6") (pintype "output"))
    )
    (net (code "16") (name "/Qbar_2") (class "Default")
      (node (ref "U5") (pin "12") (pinfunction "2D_12") (pintype "input"))
      (node (ref "U5") (pin "8") (pinfunction "2Q_8") (pintype "output"))
    )
    (net (code "17") (name "/Qbar_3") (class "Default")
      (node (ref "U51") (pin "2") (pinfunction "1D_2") (pintype "input"))
      (node (ref "U51") (pin "6") (pinfunction "1Q_6") (pintype "output"))
    )
    (net (code "18") (name "/RESET_0") (class "Default")
      (node (ref "R22") (pin "1") (pinfunction "1_1") (pintype "passive"))
    )
    (net (code "19") (name "/RESET_DIV_TO_CPLD") (class "Default")
      (node (ref "R138") (pin "1") (pinfunction "1_1") (pintype "passive"))
      (node (ref "U9") (pin "97") (pinfunction "IO_97") (pintype "bidirectional"))
    )
    (net (code "20") (name "/RESET_DIV_TO_FPGA") (class "Default")
      (node (ref "R138") (pin "2") (pinfunction "2_2") (pintype "passive+no_connect"))
    )
    (net (code "21") (name "/RESET_TX7364") (class "Default")
      (node (ref "R125") (pin "1") (pinfunction "1_1") (pintype "passive"))
      (node (ref "R22") (pin "2") (pinfunction "2_2") (pintype "passive"))
      (node (ref "R280") (pin "2") (pinfunction "2_2") (pintype "passive"))
      (node (ref "S1") (pin "2") (pinfunction "2_2") (pintype "passive"))
      (node (ref "U9") (pin "71") (pinfunction "IO_71") (pintype "bidirectional"))
    )
    (net (code "22") (name "/RST") (class "Default")
      (node (ref "R125") (pin "2") (pinfunction "2_2") (pintype "passive"))
      (node (ref "R128") (pin "2") (pinfunction "2_2") (pintype "passive"))
    )
    (net (code "23") (name "/RSTZ") (class "Default")
      (node (ref "U5") (pin "1") (pinfunction "1~{CLR}_1") (pintype "input"))
      (node (ref "U5") (pin "13") (pinfunction "2~{CLR}_13") (pintype "input"))
      (node (ref "U51") (pin "1") (pinfunction "1~{CLR}_1") (pintype "input"))
      (node (ref "U9") (pin "83") (pinfunction "IO_83") (pintype "bidirectional"))
    )
    (net (code "24") (name "/SCLKM") (class "Default")
      (node (ref "R100") (pin "2") (pinfunction "2_2") (pintype "passive"))
      (node (ref "R165") (pin "1") (pinfunction "1_1") (pintype "passive"))
      (node (ref "R234") (pin "1") (pinfunction "1_1") (pintype "passive"))
      (node (ref "R91") (pin "1") (pinfunction "1_1") (pintype "passive"))
    )
    (net (code "25") (name "/SCLKM_LVDS") (class "Default")
      (node (ref "R92") (pin "1") (pinfunction "1_1") (pintype "passive"))
      (node (ref "U9") (pin "53") (pinfunction "IO_53") (pintype "bidirectional"))
    )
    (net (code "26") (name "/SCLKP") (class "Default")
      (node (ref "R127") (pin "1") (pinfunction "1_1") (pintype "passive"))
      (node (ref "R78") (pin "1") (pinfunction "1_1") (pintype "passive"))
      (node (ref "R86") (pin "2") (pinfunction "2_2") (pintype "passive"))
      (node (ref "R91") (pin "2") (pinfunction "2_2") (pintype "passive"))
    )
    (net (code "27") (name "/SCLKP_LVDS") (class "Default")
      (node (ref "R79") (pin "1") (pinfunction "1_1") (pintype "passive"))
      (node (ref "U9") (pin "54") (pinfunction "IO_54") (pintype "bidirectional"))
    )
    (net (code "28") (name "/SCLK_CMOS") (class "Default")
      (node (ref "R78") (pin "2") (pinfunction "2_2") (pintype "passive"))
      (node (ref "TP33") (pin "1") (pintype "passive"))
      (node (ref "U9") (pin "43") (pinfunction "IO_43") (pintype "bidirectional"))
    )
    (net (code "29") (name "/SCLK_DIRECT") (class "Default")
      (node (ref "R127") (pin "2") (pinfunction "2_2") (pintype "passive"))
    )
    (net (code "30") (name "/SCLK_TO_CPLD") (class "Default")
      (node (ref "U9") (pin "85") (pinfunction "IO_85") (pintype "bidirectional"))
    )
    (net (code "31") (name "/SDATA0_DIRECT") (class "Default")
      (node (ref "R254") (pin "2") (pinfunction "2_2") (pintype "passive"))
    )
    (net (code "32") (name "/SDATA0_TO_CPLD") (class "Default")
      (node (ref "U9") (pin "89") (pinfunction "IO_89") (pintype "bidirectional"))
    )
    (net (code "33") (name "/SDATA1_TO_CPLD") (class "Default")
      (node (ref "U9") (pin "91") (pinfunction "IO_91") (pintype "bidirectional"))
    )
    (net (code "34") (name "/SDIN0_CMOS") (class "Default")
      (node (ref "R103") (pin "2") (pinfunction "2_2") (pintype "passive"))
      (node (ref "TP34") (pin "1") (pintype "passive"))
      (node (ref "U9") (pin "44") (pinfunction "IO_44") (pintype "bidirectional"))
    )
    (net (code "35") (name "/SDIN1_CMOS") (class "Default")
      (node (ref "R32") (pin "2") (pinfunction "2_2") (pintype "passive"))
      (node (ref "TP35") (pin "1") (pintype "passive"))
      (node (ref "U9") (pin "47") (pinfunction "IO_47") (pintype "bidirectional"))
    )
    (net (code "36") (name "/SDINM0") (class "Default")
      (node (ref "R109") (pin "1") (pinfunction "1_1") (pintype "passive"))
      (node (ref "R116") (pin "2") (pinfunction "2_2") (pintype "passive"))
      (node (ref "R169") (pin "1") (pinfunction "1_1") (pintype "passive"))
      (node (ref "R235") (pin "1") (pinfunction "1_1") (pintype "passive"))
    )
    (net (code "37") (name "/SDINM0_LVDS") (class "Default")
      (node (ref "R114") (pin "1") (pinfunction "1_1") (pintype "passive"))
      (node (ref "U9") (pin "55") (pinfunction "IO_55") (pintype "bidirectional"))
    )
    (net (code "38") (name "/SDINM1") (class "Default")
      (node (ref "R111") (pin "1") (pinfunction "1_1") (pintype "passive"))
      (node (ref "R163") (pin "1") (pinfunction "1_1") (pintype "passive"))
      (node (ref "R38") (pin "1") (pinfunction "1_1") (pintype "passive"))
      (node (ref "R41") (pin "2") (pinfunction "2_2") (pintype "passive"))
    )
    (net (code "39") (name "/SDINM1_LVDS") (class "Default")
      (node (ref "R39") (pin "1") (pinfunction "1_1") (pintype "passive"))
      (node (ref "U9") (pin "57") (pinfunction "IO_57") (pintype "bidirectional"))
    )
    (net (code "40") (name "/SDINP0") (class "Default")
      (node (ref "R103") (pin "1") (pinfunction "1_1") (pintype "passive"))
      (node (ref "R105") (pin "2") (pinfunction "2_2") (pintype "passive"))
      (node (ref "R109") (pin "2") (pinfunction "2_2") (pintype "passive"))
      (node (ref "R254") (pin "1") (pinfunction "1_1") (pintype "passive"))
    )
    (net (code "41") (name "/SDINP0_LVDS") (class "Default")
      (node (ref "R104") (pin "1") (pinfunction "1_1") (pintype "passive"))
      (node (ref "U9") (pin "56") (pinfunction "IO_56") (pintype "bidirectional"))
    )
    (net (code "42") (name "/SDINP1") (class "Default")
      (node (ref "R16") (pin "2") (pinfunction "2_2") (pintype "passive"))
      (node (ref "R32") (pin "1") (pinfunction "1_1") (pintype "passive"))
      (node (ref "R34") (pin "2") (pinfunction "2_2") (pintype "passive"))
      (node (ref "R38") (pin "2") (pinfunction "2_2") (pintype "passive"))
    )
    (net (code "43") (name "/SDINP1_LVDS") (class "Default")
      (node (ref "R33") (pin "1") (pinfunction "1_1") (pintype "passive"))
      (node (ref "U9") (pin "58") (pinfunction "IO_58") (pintype "bidirectional"))
    )
    (net (code "44") (name "/SDOUT") (class "Default")
      (node (ref "TP37") (pin "1") (pintype "passive"))
      (node (ref "U9") (pin "49") (pinfunction "IO_49") (pintype "bidirectional"))
    )
    (net (code "45") (name "/SDOUT_FROM_CPLD") (class "Default")
      (node (ref "U9") (pin "92") (pinfunction "IO_92") (pintype "bidirectional"))
    )
    (net (code "46") (name "/SENM") (class "Default")
      (node (ref "R233") (pin "1") (pinfunction "1_1") (pintype "passive"))
      (node (ref "R67") (pin "1") (pinfunction "1_1") (pintype "passive"))
      (node (ref "R77") (pin "2") (pinfunction "2_2") (pintype "passive"))
    )
    (net (code "47") (name "/SENM_LVDS") (class "Default")
      (node (ref "R74") (pin "1") (pinfunction "1_1") (pintype "passive"))
      (node (ref "U9") (pin "66") (pinfunction "IO_66") (pintype "bidirectional"))
    )
    (net (code "48") (name "/SENP") (class "Default")
      (node (ref "R126") (pin "1") (pinfunction "1_1") (pintype "passive"))
      (node (ref "R42") (pin "1") (pinfunction "1_1") (pintype "passive"))
      (node (ref "R65") (pin "2") (pinfunction "2_2") (pintype "passive"))
      (node (ref "R67") (pin "2") (pinfunction "2_2") (pintype "passive"))
    )
    (net (code "49") (name "/SENP_LVDS") (class "Default")
      (node (ref "R62") (pin "1") (pinfunction "1_1") (pintype "passive"))
      (node (ref "U9") (pin "67") (pinfunction "IO_67") (pintype "bidirectional"))
    )
    (net (code "50") (name "/SEN_CMOS") (class "Default")
      (node (ref "R42") (pin "2") (pinfunction "2_2") (pintype "passive"))
      (node (ref "TP36") (pin "1") (pintype "passive"))
      (node (ref "U9") (pin "48") (pinfunction "IO_48") (pintype "bidirectional"))
    )
    (net (code "51") (name "/SEN_CPLD_TO_CPLD") (class "Default")
      (node (ref "U9") (pin "87") (pinfunction "IO_87") (pintype "bidirectional"))
    )
    (net (code "52") (name "/SEN_DIRECT") (class "Default")
      (node (ref "R126") (pin "2") (pinfunction "2_2") (pintype "passive"))
    )
    (net (code "53") (name "/SEN_TX7364_TO_CPLD") (class "Default")
      (node (ref "U9") (pin "86") (pinfunction "IO_86") (pintype "bidirectional"))
    )
    (net (code "54") (name "/SP2_TO_CPLD") (class "Default")
      (node (ref "U9") (pin "98") (pinfunction "IO_98") (pintype "bidirectional"))
    )
    (net (code "55") (name "/SP3_TO_CPLD") (class "Default")
      (node (ref "U9") (pin "99") (pinfunction "IO_99") (pintype "bidirectional"))
    )
    (net (code "56") (name "/SP4_FROM_CPLD") (class "Default")
      (node (ref "U9") (pin "100") (pinfunction "IO_100") (pintype "bidirectional"))
    )
    (net (code "57") (name "/SPARE_LINE") (class "Default")
      (node (ref "TP25") (pin "1") (pintype "passive"))
      (node (ref "U9") (pin "29") (pinfunction "IO_29") (pintype "bidirectional"))
    )
    (net (code "58") (name "/SPI_MODE") (class "Default")
      (node (ref "TP24") (pin "1") (pintype "passive"))
      (node (ref "U9") (pin "27") (pinfunction "IO_27") (pintype "bidirectional"))
    )
    (net (code "59") (name "/STDBY") (class "Default")
      (node (ref "TP22") (pin "1") (pintype "passive"))
      (node (ref "U9") (pin "28") (pinfunction "IO_28") (pintype "bidirectional"))
    )
    (net (code "60") (name "/SYNCHRONIZER") (class "Default")
      (node (ref "TP23") (pin "1") (pintype "passive"))
      (node (ref "U9") (pin "1") (pinfunction "IO_1") (pintype "bidirectional"))
    )
    (net (code "61") (name "/SYNCM") (class "Default")
      (node (ref "R21") (pin "1") (pinfunction "1_1") (pintype "passive"))
      (node (ref "R23") (pin "1") (pinfunction "1_1") (pintype "passive"))
      (node (ref "R274") (pin "1") (pinfunction "1_1") (pintype "passive"))
      (node (ref "R31") (pin "2") (pinfunction "2_2") (pintype "passive"))
    )
    (net (code "62") (name "/SYNCM_LVDS") (class "Default")
      (node (ref "R31") (pin "1") (pinfunction "1_1") (pintype "passive"))
      (node (ref "U9") (pin "73") (pinfunction "IO_73") (pintype "bidirectional"))
    )
    (net (code "63") (name "/SYNCM_LVDS_EXT") (class "Default")
      (node (ref "R274") (pin "2") (pinfunction "2_2") (pintype "passive"))
    )
    (net (code "64") (name "/SYNCP") (class "Default")
      (node (ref "R19") (pin "2") (pinfunction "2_2") (pintype "passive"))
      (node (ref "R21") (pin "2") (pinfunction "2_2") (pintype "passive"))
      (node (ref "R23") (pin "2") (pinfunction "2_2") (pintype "passive"))
      (node (ref "R273") (pin "1") (pinfunction "1_1") (pintype "passive"))
    )
    (net (code "65") (name "/SYNCP_LVDS") (class "Default")
      (node (ref "R19") (pin "1") (pinfunction "1_1") (pintype "passive"))
      (node (ref "U9") (pin "74") (pinfunction "IO_74") (pintype "bidirectional"))
    )
    (net (code "66") (name "/SYNCP_LVDS_EXT") (class "Default")
      (node (ref "R273") (pin "2") (pinfunction "2_2") (pintype "passive"))
    )
    (net (code "67") (name "/SYNC_FPGA") (class "Default")
      (node (ref "U9") (pin "76") (pinfunction "IO_76") (pintype "bidirectional+no_connect"))
    )
    (net (code "68") (name "/SYNC_TP") (class "Default")
      (node (ref "TP20") (pin "1") (pintype "passive"))
      (node (ref "U9") (pin "75") (pinfunction "IO_75") (pintype "bidirectional"))
    )
    (net (code "69") (name "/TCK") (class "Default")
      (node (ref "C162") (pin "2") (pinfunction "2_2") (pintype "passive"))
      (node (ref "R24") (pin "2") (pinfunction "2_2") (pintype "passive"))
      (node (ref "R27") (pin "1") (pinfunction "1_1") (pintype "passive"))
      (node (ref "U9") (pin "24") (pinfunction "TCK_24") (pintype "input"))
    )
    (net (code "70") (name "/TCK_TO_CPLD") (class "Default")
      (node (ref "R24") (pin "1") (pinfunction "1_1") (pintype "passive"))
    )
    (net (code "71") (name "/TDI") (class "Default")
      (node (ref "C165") (pin "2") (pinfunction "2_2") (pintype "passive"))
      (node (ref "R132") (pin "2") (pinfunction "2_2") (pintype "passive"))
      (node (ref "R133") (pin "1") (pinfunction "1_1") (pintype "passive"))
      (node (ref "U9") (pin "23") (pinfunction "TDI_23") (pintype "input"))
    )
    (net (code "72") (name "/TDI_TO_CPLD") (class "Default")
      (node (ref "R132") (pin "1") (pinfunction "1_1") (pintype "passive"))
    )
    (net (code "73") (name "/TDO") (class "Default")
      (node (ref "C163") (pin "2") (pinfunction "2_2") (pintype "passive"))
      (node (ref "R28") (pin "2") (pinfunction "2_2") (pintype "passive"))
      (node (ref "R37") (pin "1") (pinfunction "1_1") (pintype "passive"))
      (node (ref "U9") (pin "25") (pinfunction "TDO_25") (pintype "output"))
    )
    (net (code "74") (name "/TDO_FROM_CPLD") (class "Default")
      (node (ref "R28") (pin "1") (pinfunction "1_1") (pintype "passive"))
    )
    (net (code "75") (name "/TMS") (class "Default")
      (node (ref "C164") (pin "2") (pinfunction "2_2") (pintype "passive"))
      (node (ref "R131") (pin "1") (pinfunction "1_1") (pintype "passive"))
      (node (ref "R40") (pin "2") (pinfunction "2_2") (pintype "passive"))
      (node (ref "U9") (pin "22") (pinfunction "TMS_22") (pintype "input"))
    )
    (net (code "76") (name "/TMS_TO_CPLD") (class "Default")
      (node (ref "R40") (pin "1") (pinfunction "1_1") (pintype "passive"))
    )
    (net (code "77") (name "/TSHUT_FUNC") (class "Default")
      (node (ref "U9") (pin "34") (pinfunction "IO_34") (pintype "bidirectional"))
    )
    (net (code "78") (name "/TX_RXZ_FUNC") (class "Default")
      (node (ref "U9") (pin "30") (pinfunction "IO_30") (pintype "bidirectional"))
    )
    (net (code "79") (name "/V_+5V") (class "Default")
      (node (ref "R112") (pin "1") (pinfunction "1_1") (pintype "passive"))
      (node (ref "R115") (pin "1") (pinfunction "1_1") (pintype "passive"))
      (node (ref "R18") (pin "1") (pinfunction "1_1") (pintype "passive"))
    )
    (net (code "80") (name "/V_1P8_CPLD") (class "Default")
      (node (ref "C112") (pin "1") (pinfunction "1_1") (pintype "passive"))
      (node (ref "C113") (pin "1") (pinfunction "1_1") (pintype "passive"))
      (node (ref "C114") (pin "1") (pinfunction "1_1") (pintype "passive"))
      (node (ref "C115") (pin "1") (pinfunction "1_1") (pintype "passive"))
      (node (ref "C116") (pin "1") (pinfunction "1_1") (pintype "passive"))
      (node (ref "C117") (pin "1") (pinfunction "1_1") (pintype "passive"))
      (node (ref "C118") (pin "1") (pinfunction "1_1") (pintype "passive"))
      (node (ref "U9") (pin "13") (pinfunction "VCCINT_13") (pintype "power_in"))
      (node (ref "U9") (pin "31") (pinfunction "VCCIO1_31") (pintype "power_in"))
      (node (ref "U9") (pin "39") (pinfunction "VCCINT_39") (pintype "power_in"))
      (node (ref "U9") (pin "45") (pinfunction "VCCIO1_45") (pintype "power_in"))
      (node (ref "U9") (pin "63") (pinfunction "VCCINT_63") (pintype "power_in"))
      (node (ref "U9") (pin "88") (pinfunction "VCCINT_88") (pintype "power_in"))
      (node (ref "U9") (pin "9") (pinfunction "VCCIO1_9") (pintype "power_in"))
    )
    (net (code "81") (name "/V_2P5_CPLD") (class "Default")
      (node (ref "C108") (pin "1") (pinfunction "1_1") (pintype "passive"))
      (node (ref "C109") (pin "1") (pinfunction "1_1") (pintype "passive"))
      (node (ref "C110") (pin "1") (pinfunction "1_1") (pintype "passive"))
      (node (ref "C111") (pin "1") (pinfunction "1_1") (pintype "passive"))
      (node (ref "C121") (pin "1") (pinfunction "1_1") (pintype "passive"))
      (node (ref "C122") (pin "1") (pinfunction "1_1") (pintype "passive"))
      (node (ref "C123") (pin "1") (pinfunction "1_1") (pintype "passive"))
      (node (ref "C160") (pin "1") (pinfunction "1_1") (pintype "passive"))
      (node (ref "U11") (pin "1") (pinfunction "VCC_1") (pintype "passive"))
      (node (ref "U5") (pin "10") (pinfunction "2~{PRE}_10") (pintype "input"))
      (node (ref "U5") (pin "14") (pinfunction "VCC_14") (pintype "power_in"))
      (node (ref "U5") (pin "4") (pinfunction "1~{PRE}_4") (pintype "input"))
      (node (ref "U51") (pin "10") (pinfunction "2~{PRE}_10") (pintype "input"))
      (node (ref "U51") (pin "13") (pinfunction "2~{CLR}_13") (pintype "input"))
      (node (ref "U51") (pin "14") (pinfunction "VCC_14") (pintype "power_in"))
      (node (ref "U51") (pin "4") (pinfunction "1~{PRE}_4") (pintype "input"))
      (node (ref "U9") (pin "59") (pinfunction "VCCIO2_59") (pintype "power_in"))
      (node (ref "U9") (pin "80") (pinfunction "VCCIO2_80") (pintype "power_in"))
      (node (ref "U9") (pin "94") (pinfunction "VCCIO2_94") (pintype "power_in"))
    )
    (net (code "82") (name "/WAKE_UP") (class "Default")
      (node (ref "TP27") (pin "1") (pintype "passive"))
      (node (ref "U9") (pin "35") (pinfunction "IO_35") (pintype "bidirectional"))
    )
    (net (code "83") (name "GND") (class "Default")
      (node (ref "C108") (pin "2") (pinfunction "2_2") (pintype "passive"))
      (node (ref "C109") (pin "2") (pinfunction "2_2") (pintype "passive"))
      (node (ref "C110") (pin "2") (pinfunction "2_2") (pintype "passive"))
      (node (ref "C111") (pin "2") (pinfunction "2_2") (pintype "passive"))
      (node (ref "C112") (pin "2") (pinfunction "2_2") (pintype "passive"))
      (node (ref "C113") (pin "2") (pinfunction "2_2") (pintype "passive"))
      (node (ref "C114") (pin "2") (pinfunction "2_2") (pintype "passive"))
      (node (ref "C115") (pin "2") (pinfunction "2_2") (pintype "passive"))
      (node (ref "C116") (pin "2") (pinfunction "2_2") (pintype "passive"))
      (node (ref "C117") (pin "2") (pinfunction "2_2") (pintype "passive"))
      (node (ref "C118") (pin "2") (pinfunction "2_2") (pintype "passive"))
      (node (ref "C121") (pin "2") (pinfunction "2_2") (pintype "passive"))
      (node (ref "C122") (pin "2") (pinfunction "2_2") (pintype "passive"))
      (node (ref "C123") (pin "2") (pinfunction "2_2") (pintype "passive"))
      (node (ref "C160") (pin "2") (pinfunction "2_2") (pintype "passive"))
      (node (ref "C162") (pin "1") (pinfunction "1_1") (pintype "passive"))
      (node (ref "C163") (pin "1") (pinfunction "1_1") (pintype "passive"))
      (node (ref "C164") (pin "1") (pinfunction "1_1") (pintype "passive"))
      (node (ref "C165") (pin "1") (pinfunction "1_1") (pintype "passive"))
      (node (ref "J11") (pin "10") (pinfunction "10_10") (pintype "passive"))
      (node (ref "J11") (pin "2") (pinfunction "2_2") (pintype "passive"))
      (node (ref "J8") (pin "2") (pinfunction "2_2") (pintype "passive"))
      (node (ref "J8") (pin "3") (pinfunction "3_3") (pintype "passive"))
      (node (ref "J8") (pin "4") (pinfunction "4_4") (pintype "passive"))
      (node (ref "J8") (pin "5") (pinfunction "5_5") (pintype "passive"))
      (node (ref "R113") (pin "1") (pinfunction "1_1") (pintype "passive"))
      (node (ref "R120") (pin "1") (pinfunction "1_1") (pintype "passive"))
      (node (ref "R16") (pin "1") (pinfunction "1_1") (pintype "passive"))
      (node (ref "R163") (pin "2") (pinfunction "2_2") (pintype "passive"))
      (node (ref "R165") (pin "2") (pinfunction "2_2") (pintype "passive"))
      (node (ref "R169") (pin "2") (pinfunction "2_2") (pintype "passive"))
      (node (ref "R233") (pin "2") (pinfunction "2_2") (pintype "passive"))
      (node (ref "R280") (pin "1") (pinfunction "1_1") (pintype "passive"))
      (node (ref "R72") (pin "1") (pinfunction "1_1") (pintype "passive"))
      (node (ref "U11") (pin "2") (pinfunction "GND_2") (pintype "power_in"))
      (node (ref "U5") (pin "15") (pinfunction "EP_15") (pintype "passive"))
      (node (ref "U5") (pin "7") (pinfunction "GND_7") (pintype "power_in"))
      (node (ref "U51") (pin "11") (pinfunction "2CLK_11") (pintype "input"))
      (node (ref "U51") (pin "12") (pinfunction "2D_12") (pintype "input"))
      (node (ref "U51") (pin "15") (pinfunction "EP_15") (pintype "passive"))
      (node (ref "U51") (pin "7") (pinfunction "GND_7") (pintype "power_in"))
      (node (ref "U9") (pin "10") (pinfunction "GND_10") (pintype "power_in"))
      (node (ref "U9") (pin "11") (pinfunction "GND_11") (pintype "power_in"))
      (node (ref "U9") (pin "32") (pinfunction "GND_32") (pintype "power_in"))
      (node (ref "U9") (pin "37") (pinfunction "GND_37") (pintype "power_in"))
      (node (ref "U9") (pin "46") (pinfunction "GND_46") (pintype "power_in"))
      (node (ref "U9") (pin "60") (pinfunction "GND_60") (pintype "power_in"))
      (node (ref "U9") (pin "65") (pinfunction "GND_65") (pintype "power_in"))
      (node (ref "U9") (pin "79") (pinfunction "GND_79") (pintype "power_in"))
      (node (ref "U9") (pin "8") (pinfunction "GND_8") (pintype "power_in"))
      (node (ref "U9") (pin "90") (pinfunction "GND_90") (pintype "power_in"))
      (node (ref "U9") (pin "93") (pinfunction "GND_93") (pintype "power_in"))
      (node (ref "U9") (pin "95") (pinfunction "GND_95") (pintype "power_in"))
    )
    (net (code "84") (name "Net-(J11-Pad1)") (class "Default")
      (node (ref "J11") (pin "1") (pinfunction "1_1") (pintype "passive"))
      (node (ref "R27") (pin "2") (pinfunction "2_2") (pintype "passive"))
    )
    (net (code "85") (name "Net-(J11-Pad3)") (class "Default")
      (node (ref "J11") (pin "3") (pinfunction "3_3") (pintype "passive"))
      (node (ref "R37") (pin "2") (pinfunction "2_2") (pintype "passive"))
    )
    (net (code "86") (name "Net-(J11-Pad5)") (class "Default")
      (node (ref "J11") (pin "5") (pinfunction "5_5") (pintype "passive"))
      (node (ref "R131") (pin "2") (pinfunction "2_2") (pintype "passive"))
    )
    (net (code "87") (name "Net-(J11-Pad9)") (class "Default")
      (node (ref "J11") (pin "9") (pinfunction "9_9") (pintype "passive"))
      (node (ref "R133") (pin "2") (pinfunction "2_2") (pintype "passive"))
    )
    (net (code "88") (name "Net-(R18-Pad2)") (class "Default")
      (node (ref "R18") (pin "2") (pinfunction "2_2") (pintype "passive"))
      (node (ref "S1") (pin "1") (pinfunction "1_1") (pintype "passive"))
    )
    (net (code "89") (name "Net-(R33-Pad2)") (class "Default")
      (node (ref "R33") (pin "2") (pinfunction "2_2") (pintype "passive"))
      (node (ref "R34") (pin "1") (pinfunction "1_1") (pintype "passive"))
      (node (ref "R35") (pin "2") (pinfunction "2_2") (pintype "passive"))
    )
    (net (code "90") (name "Net-(R35-Pad1)") (class "Default")
      (node (ref "R35") (pin "1") (pinfunction "1_1") (pintype "passive"))
      (node (ref "R39") (pin "2") (pinfunction "2_2") (pintype "passive"))
      (node (ref "R41") (pin "1") (pinfunction "1_1") (pintype "passive"))
    )
    (net (code "91") (name "Net-(R62-Pad2)") (class "Default")
      (node (ref "R62") (pin "2") (pinfunction "2_2") (pintype "passive"))
      (node (ref "R65") (pin "1") (pinfunction "1_1") (pintype "passive"))
      (node (ref "R66") (pin "2") (pinfunction "2_2") (pintype "passive"))
    )
    (net (code "92") (name "Net-(R66-Pad1)") (class "Default")
      (node (ref "R66") (pin "1") (pinfunction "1_1") (pintype "passive"))
      (node (ref "R74") (pin "2") (pinfunction "2_2") (pintype "passive"))
      (node (ref "R77") (pin "1") (pinfunction "1_1") (pintype "passive"))
    )
    (net (code "93") (name "Net-(R79-Pad2)") (class "Default")
      (node (ref "R79") (pin "2") (pinfunction "2_2") (pintype "passive"))
      (node (ref "R86") (pin "1") (pinfunction "1_1") (pintype "passive"))
      (node (ref "R89") (pin "2") (pinfunction "2_2") (pintype "passive"))
    )
    (net (code "94") (name "Net-(R100-Pad1)") (class "Default")
      (node (ref "R100") (pin "1") (pinfunction "1_1") (pintype "passive"))
      (node (ref "R89") (pin "1") (pinfunction "1_1") (pintype "passive"))
      (node (ref "R92") (pin "2") (pinfunction "2_2") (pintype "passive"))
    )
    (net (code "95") (name "Net-(R104-Pad2)") (class "Default")
      (node (ref "R104") (pin "2") (pinfunction "2_2") (pintype "passive"))
      (node (ref "R105") (pin "1") (pinfunction "1_1") (pintype "passive"))
      (node (ref "R108") (pin "2") (pinfunction "2_2") (pintype "passive"))
    )
    (net (code "96") (name "Net-(R108-Pad1)") (class "Default")
      (node (ref "R108") (pin "1") (pinfunction "1_1") (pintype "passive"))
      (node (ref "R114") (pin "2") (pinfunction "2_2") (pintype "passive"))
      (node (ref "R116") (pin "1") (pinfunction "1_1") (pintype "passive"))
    )
    (net (code "97") (name "Net-(R112-Pad2)") (class "Default")
      (node (ref "R112") (pin "2") (pinfunction "2_2") (pintype "passive"))
      (node (ref "S2") (pin "1") (pinfunction "1_1") (pintype "passive"))
    )
    (net (code "98") (name "Net-(R115-Pad2)") (class "Default")
      (node (ref "R115") (pin "2") (pinfunction "2_2") (pintype "passive"))
      (node (ref "S3") (pin "1") (pinfunction "1_1") (pintype "passive"))
    )
    (net (code "99") (name "Net-(R128-Pad1)") (class "Default")
      (node (ref "R128") (pin "1") (pinfunction "1_1") (pintype "passive"))
      (node (ref "U9") (pin "36") (pinfunction "IO_36") (pintype "bidirectional"))
    )
    (net (code "100") (name "Net-(TP38-Pad1)") (class "Default")
      (node (ref "TP38") (pin "1") (pintype "passive"))
      (node (ref "U9") (pin "2") (pinfunction "IO_2") (pintype "bidirectional"))
    )
    (net (code "101") (name "Net-(TP39-Pad1)") (class "Default")
      (node (ref "TP39") (pin "1") (pintype "passive"))
      (node (ref "U9") (pin "3") (pinfunction "IO_3") (pintype "bidirectional"))
    )
    (net (code "102") (name "Net-(U5B-2CLK)") (class "Default")
      (node (ref "U5") (pin "11") (pinfunction "2CLK_11") (pintype "input"))
      (node (ref "U5") (pin "5") (pinfunction "1Q_5") (pintype "output"))
    )
    (net (code "103") (name "Net-(U51A-1CLK)") (class "Default")
      (node (ref "U5") (pin "9") (pinfunction "2Q_9") (pintype "output"))
      (node (ref "U51") (pin "3") (pinfunction "1CLK_3") (pintype "input"))
    )
    (net (code "104") (name "V_1P8") (class "Default")
      (node (ref "J11") (pin "4") (pinfunction "4_4") (pintype "passive"))
    )
    (net (code "105") (name "unconnected-(J11-Pad6)") (class "Default")
      (node (ref "J11") (pin "6") (pinfunction "6_6") (pintype "passive+no_connect"))
    )
    (net (code "106") (name "unconnected-(J11-Pad7)") (class "Default")
      (node (ref "J11") (pin "7") (pinfunction "7_7") (pintype "passive+no_connect"))
    )
    (net (code "107") (name "unconnected-(J11-Pad8)") (class "Default")
      (node (ref "J11") (pin "8") (pinfunction "8_8") (pintype "passive+no_connect"))
    )
    (net (code "108") (name "unconnected-(U9-IO-Pad4)") (class "Default")
      (node (ref "U9") (pin "4") (pinfunction "IO_4") (pintype "bidirectional"))
    )
    (net (code "109") (name "unconnected-(U9-IO-Pad5)") (class "Default")
      (node (ref "U9") (pin "5") (pinfunction "IO_5") (pintype "bidirectional"))
    )
    (net (code "110") (name "unconnected-(U9-IO-Pad6)") (class "Default")
      (node (ref "U9") (pin "6") (pinfunction "IO_6") (pintype "bidirectional"))
    )
    (net (code "111") (name "unconnected-(U9-IO-Pad7)") (class "Default")
      (node (ref "U9") (pin "7") (pinfunction "IO_7") (pintype "bidirectional"))
    )
    (net (code "112") (name "unconnected-(U9-IO-Pad12)") (class "Default")
      (node (ref "U9") (pin "12") (pinfunction "IO_12") (pintype "bidirectional"))
    )
    (net (code "113") (name "unconnected-(U9-IO-Pad15)") (class "Default")
      (node (ref "U9") (pin "15") (pinfunction "IO_15") (pintype "bidirectional"))
    )
    (net (code "114") (name "unconnected-(U9-IO-Pad16)") (class "Default")
      (node (ref "U9") (pin "16") (pinfunction "IO_16") (pintype "bidirectional"))
    )
    (net (code "115") (name "unconnected-(U9-IO-Pad17)") (class "Default")
      (node (ref "U9") (pin "17") (pinfunction "IO_17") (pintype "bidirectional"))
    )
    (net (code "116") (name "unconnected-(U9-IO-Pad18)") (class "Default")
      (node (ref "U9") (pin "18") (pinfunction "IO_18") (pintype "bidirectional"))
    )
    (net (code "117") (name "unconnected-(U9-IO-Pad19)") (class "Default")
      (node (ref "U9") (pin "19") (pinfunction "IO_19") (pintype "bidirectional"))
    )
    (net (code "118") (name "unconnected-(U9-IO-Pad20)") (class "Default")
      (node (ref "U9") (pin "20") (pinfunction "IO_20") (pintype "bidirectional"))
    )
    (net (code "119") (name "unconnected-(U9-IO-Pad21)") (class "Default")
      (node (ref "U9") (pin "21") (pinfunction "IO_21") (pintype "bidirectional"))
    )
    (net (code "120") (name "unconnected-(U9-IO-Pad26)") (class "Default")
      (node (ref "U9") (pin "26") (pinfunction "IO_26") (pintype "bidirectional"))
    )
    (net (code "121") (name "unconnected-(U9-IO-Pad50)") (class "Default")
      (node (ref "U9") (pin "50") (pinfunction "IO_50") (pintype "bidirectional"))
    )
    (net (code "122") (name "unconnected-(U9-IO-Pad51)") (class "Default")
      (node (ref "U9") (pin "51") (pinfunction "IO_51") (pintype "bidirectional"))
    )
    (net (code "123") (name "unconnected-(U9-IO-Pad52)") (class "Default")
      (node (ref "U9") (pin "52") (pinfunction "IO_52") (pintype "bidirectional"))
    )
    (net (code "124") (name "unconnected-(U9-IO-Pad61)") (class "Default")
      (node (ref "U9") (pin "61") (pinfunction "IO_61") (pintype "bidirectional"))
    )
    (net (code "125") (name "unconnected-(U9-IO-Pad62)") (class "Default")
      (node (ref "U9") (pin "62") (pinfunction "IO_62") (pintype "bidirectional"))
    )
    (net (code "126") (name "unconnected-(U9-IO-Pad64)") (class "Default")
      (node (ref "U9") (pin "64") (pinfunction "IO_64") (pintype "bidirectional"))
    )
    (net (code "127") (name "unconnected-(U9-IO-Pad68)") (class "Default")
      (node (ref "U9") (pin "68") (pinfunction "IO_68") (pintype "bidirectional"))
    )
    (net (code "128") (name "unconnected-(U9-IO-Pad72)") (class "Default")
      (node (ref "U9") (pin "72") (pinfunction "IO_72") (pintype "bidirectional"))
    )
    (net (code "129") (name "unconnected-(U9-IO-Pad77)") (class "Default")
      (node (ref "U9") (pin "77") (pinfunction "IO_77") (pintype "bidirectional"))
    )
    (net (code "130") (name "unconnected-(U9-IO-Pad78)") (class "Default")
      (node (ref "U9") (pin "78") (pinfunction "IO_78") (pintype "bidirectional"))
    )
    (net (code "131") (name "unconnected-(U9-IO-Pad81)") (class "Default")
      (node (ref "U9") (pin "81") (pinfunction "IO_81") (pintype "bidirectional"))
    )
    (net (code "132") (name "unconnected-(U51B-2Q-Pad8)") (class "Default")
      (node (ref "U51") (pin "8") (pinfunction "2Q_8") (pintype "output"))
    )
    (net (code "133") (name "unconnected-(U51B-2Q-Pad9)") (class "Default")
      (node (ref "U51") (pin "9") (pinfunction "2Q_9") (pintype "output"))
    )
  )
)
